# PSRAM_SPI.net
KiCad netlist of a schematic drawn in Altium Designer
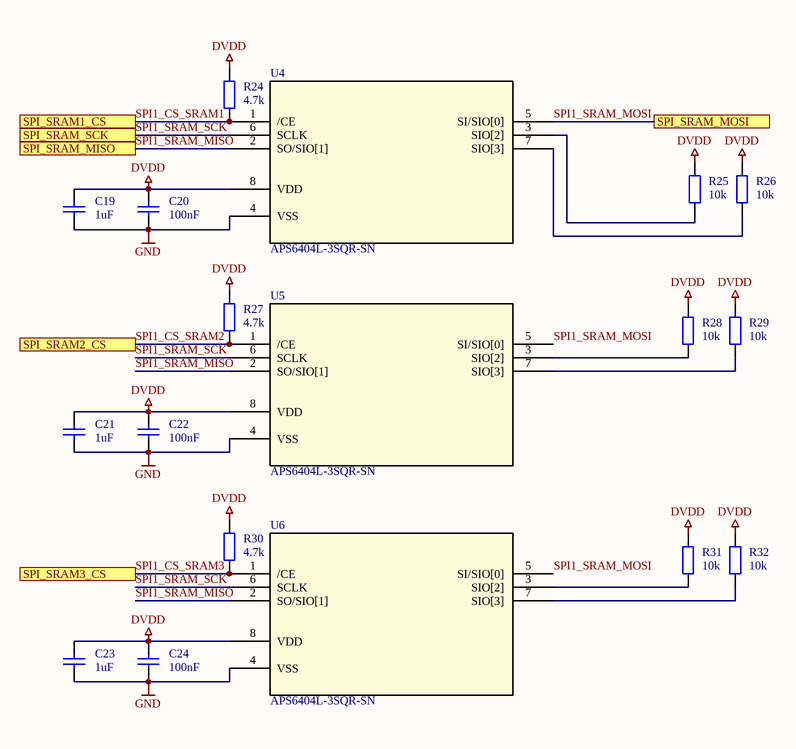
[diagram p0: PSRAM_SPI.SchDoc]

(export (version "E")
  (design (tool "Eeschema 10.0.6"))
  (components
    (comp (ref "C19")
      (value "1uF")
      (footprint "C1206-KUE")
      (description "Capacitor")
      (fields (field (name "MANUFACTURER") "Kemet") (field (name "PUBLISHER") "Altium Limited"))
      (libsource (lib "ExtrapartsKUE_V01") (part "Capacitor"))
    )
    (comp (ref "C20")
      (value "100nF")
      (footprint "C1206-KUE")
      (description "Capacitor")
      (fields (field (name "MANUFACTURER") "Kemet") (field (name "PUBLISHER") "Altium Limited"))
      (libsource (lib "ExtrapartsKUE_V01") (part "Capacitor"))
    )
    (comp (ref "C21")
      (value "1uF")
      (footprint "C1206-KUE")
      (description "Capacitor")
      (fields (field (name "MANUFACTURER") "Kemet") (field (name "PUBLISHER") "Altium Limited"))
      (libsource (lib "ExtrapartsKUE_V01") (part "Capacitor"))
    )
    (comp (ref "C22")
      (value "100nF")
      (footprint "C1206-KUE")
      (description "Capacitor")
      (fields (field (name "MANUFACTURER") "Kemet") (field (name "PUBLISHER") "Altium Limited"))
      (libsource (lib "ExtrapartsKUE_V01") (part "Capacitor"))
    )
    (comp (ref "C23")
      (value "1uF")
      (footprint "C1206-KUE")
      (description "Capacitor")
      (fields (field (name "MANUFACTURER") "Kemet") (field (name "PUBLISHER") "Altium Limited"))
      (libsource (lib "ExtrapartsKUE_V01") (part "Capacitor"))
    )
    (comp (ref "C24")
      (value "100nF")
      (footprint "C1206-KUE")
      (description "Capacitor")
      (fields (field (name "MANUFACTURER") "Kemet") (field (name "PUBLISHER") "Altium Limited"))
      (libsource (lib "ExtrapartsKUE_V01") (part "Capacitor"))
    )
    (comp (ref "R24")
      (value "4.7k")
      (footprint "C1206-KUE")
      (description "Resistor SMD")
      (fields (field (name "MANUFACTURER") "AVX") (field (name "PUBLISHER") "Altium Limited"))
      (libsource (lib "ExtrapartsKUE_V01") (part "ResistorSMD"))
    )
    (comp (ref "R25")
      (value "10k")
      (footprint "C1206-KUE")
      (description "Resistor SMD")
      (fields (field (name "MANUFACTURER") "AVX") (field (name "PUBLISHER") "Altium Limited"))
      (libsource (lib "ExtrapartsKUE_V01") (part "ResistorSMD"))
    )
    (comp (ref "R26")
      (value "10k")
      (footprint "C1206-KUE")
      (description "Resistor SMD")
      (fields (field (name "MANUFACTURER") "AVX") (field (name "PUBLISHER") "Altium Limited"))
      (libsource (lib "ExtrapartsKUE_V01") (part "ResistorSMD"))
    )
    (comp (ref "R27")
      (value "4.7k")
      (footprint "C1206-KUE")
      (description "Resistor SMD")
      (fields (field (name "MANUFACTURER") "AVX") (field (name "PUBLISHER") "Altium Limited"))
      (libsource (lib "ExtrapartsKUE_V01") (part "ResistorSMD"))
    )
    (comp (ref "R28")
      (value "10k")
      (footprint "C1206-KUE")
      (description "Resistor SMD")
      (fields (field (name "MANUFACTURER") "AVX") (field (name "PUBLISHER") "Altium Limited"))
      (libsource (lib "ExtrapartsKUE_V01") (part "ResistorSMD"))
    )
    (comp (ref "R29")
      (value "10k")
      (footprint "C1206-KUE")
      (description "Resistor SMD")
      (fields (field (name "MANUFACTURER") "AVX") (field (name "PUBLISHER") "Altium Limited"))
      (libsource (lib "ExtrapartsKUE_V01") (part "ResistorSMD"))
    )
    (comp (ref "R30")
      (value "4.7k")
      (footprint "C1206-KUE")
      (description "Resistor SMD")
      (fields (field (name "MANUFACTURER") "AVX") (field (name "PUBLISHER") "Altium Limited"))
      (libsource (lib "ExtrapartsKUE_V01") (part "ResistorSMD"))
    )
    (comp (ref "R31")
      (value "10k")
      (footprint "C1206-KUE")
      (description "Resistor SMD")
      (fields (field (name "MANUFACTURER") "AVX") (field (name "PUBLISHER") "Altium Limited"))
      (libsource (lib "ExtrapartsKUE_V01") (part "ResistorSMD"))
    )
    (comp (ref "R32")
      (value "10k")
      (footprint "C1206-KUE")
      (description "Resistor SMD")
      (fields (field (name "MANUFACTURER") "AVX") (field (name "PUBLISHER") "Altium Limited"))
      (libsource (lib "ExtrapartsKUE_V01") (part "ResistorSMD"))
    )
    (comp (ref "U4")
      (value "APS6404L-3SQR-SN")
      (footprint "APS6404L-3SQR-SN_APY")
      (description "Description")
      (fields (field (name "COPYRIGHT") "Copyright (C) 2025 Ultra Librarian. All rights reserved."))
      (libsource (lib "APS6404L-3SQR-SN") (part "APS6404L-3SQR-SN"))
    )
    (comp (ref "U5")
      (value "APS6404L-3SQR-SN")
      (footprint "APS6404L-3SQR-SN_APY")
      (description "Description")
      (fields (field (name "COPYRIGHT") "Copyright (C) 2025 Ultra Librarian. All rights reserved."))
      (libsource (lib "APS6404L-3SQR-SN") (part "APS6404L-3SQR-SN"))
    )
    (comp (ref "U6")
      (value "APS6404L-3SQR-SN")
      (footprint "APS6404L-3SQR-SN_APY")
      (description "Description")
      (fields (field (name "COPYRIGHT") "Copyright (C) 2025 Ultra Librarian. All rights reserved."))
      (libsource (lib "APS6404L-3SQR-SN") (part "APS6404L-3SQR-SN"))
    )
  )
  (nets
    (net (code "1") (name "/SPI1_CS_SRAM1") (class "Default")
      (node (ref "R24") (pin "2") (pinfunction "2_2") (pintype "passive"))
      (node (ref "U4") (pin "1") (pinfunction "/CE_1") (pintype "passive"))
    )
    (net (code "2") (name "/SPI1_CS_SRAM2") (class "Default")
      (node (ref "R27") (pin "2") (pinfunction "2_2") (pintype "passive"))
      (node (ref "U5") (pin "1") (pinfunction "/CE_1") (pintype "passive"))
    )
    (net (code "3") (name "/SPI1_CS_SRAM3") (class "Default")
      (node (ref "R30") (pin "2") (pinfunction "2_2") (pintype "passive"))
      (node (ref "U6") (pin "1") (pinfunction "/CE_1") (pintype "passive"))
    )
    (net (code "4") (name "/SPI1_SRAM_MISO") (class "Default")
      (node (ref "U4") (pin "2") (pinfunction "SO/SIO[1]_2") (pintype "passive"))
      (node (ref "U5") (pin "2") (pinfunction "SO/SIO[1]_2") (pintype "passive"))
      (node (ref "U6") (pin "2") (pinfunction "SO/SIO[1]_2") (pintype "passive"))
    )
    (net (code "5") (name "/SPI1_SRAM_MOSI") (class "Default")
      (node (ref "U4") (pin "5") (pinfunction "SI/SIO[0]_5") (pintype "passive"))
      (node (ref "U5") (pin "5") (pinfunction "SI/SIO[0]_5") (pintype "passive"))
      (node (ref "U6") (pin "5") (pinfunction "SI/SIO[0]_5") (pintype "passive"))
    )
    (net (code "6") (name "/SPI1_SRAM_SCK") (class "Default")
      (node (ref "U4") (pin "6") (pinfunction "SCLK_6") (pintype "passive"))
      (node (ref "U5") (pin "6") (pinfunction "SCLK_6") (pintype "passive"))
      (node (ref "U6") (pin "6") (pinfunction "SCLK_6") (pintype "passive"))
    )
    (net (code "7") (name "DVDD") (class "Default")
      (node (ref "C19") (pin "2") (pinfunction "2_2") (pintype "passive"))
      (node (ref "C20") (pin "2") (pinfunction "2_2") (pintype "passive"))
      (node (ref "C21") (pin "2") (pinfunction "2_2") (pintype "passive"))
      (node (ref "C22") (pin "2") (pinfunction "2_2") (pintype "passive"))
      (node (ref "C23") (pin "2") (pinfunction "2_2") (pintype "passive"))
      (node (ref "C24") (pin "2") (pinfunction "2_2") (pintype "passive"))
      (node (ref "R24") (pin "1") (pinfunction "1_1") (pintype "passive"))
      (node (ref "R25") (pin "1") (pinfunction "1_1") (pintype "passive"))
      (node (ref "R26") (pin "1") (pinfunction "1_1") (pintype "passive"))
      (node (ref "R27") (pin "1") (pinfunction "1_1") (pintype "passive"))
      (node (ref "R28") (pin "1") (pinfunction "1_1") (pintype "passive"))
      (node (ref "R29") (pin "1") (pinfunction "1_1") (pintype "passive"))
      (node (ref "R30") (pin "1") (pinfunction "1_1") (pintype "passive"))
      (node (ref "R31") (pin "1") (pinfunction "1_1") (pintype "passive"))
      (node (ref "R32") (pin "1") (pinfunction "1_1") (pintype "passive"))
      (node (ref "U4") (pin "8") (pinfunction "VDD_8") (pintype "passive"))
      (node (ref "U5") (pin "8") (pinfunction "VDD_8") (pintype "passive"))
      (node (ref "U6") (pin "8") (pinfunction "VDD_8") (pintype "passive"))
    )
    (net (code "8") (name "GND") (class "Default")
      (node (ref "C19") (pin "1") (pinfunction "1_1") (pintype "passive"))
      (node (ref "C20") (pin "1") (pinfunction "1_1") (pintype "passive"))
      (node (ref "C21") (pin "1") (pinfunction "1_1") (pintype "passive"))
      (node (ref "C22") (pin "1") (pinfunction "1_1") (pintype "passive"))
      (node (ref "C23") (pin "1") (pinfunction "1_1") (pintype "passive"))
      (node (ref "C24") (pin "1") (pinfunction "1_1") (pintype "passive"))
      (node (ref "U4") (pin "4") (pinfunction "VSS_4") (pintype "passive"))
      (node (ref "U5") (pin "4") (pinfunction "VSS_4") (pintype "passive"))
      (node (ref "U6") (pin "4") (pinfunction "VSS_4") (pintype "passive"))
    )
    (net (code "9") (name "Net-(U4-SIO[2])") (class "Default")
      (node (ref "R25") (pin "2") (pinfunction "2_2") (pintype "passive"))
      (node (ref "U4") (pin "3") (pinfunction "SIO[2]_3") (pintype "passive"))
    )
    (net (code "10") (name "Net-(U4-SIO[3])") (class "Default")
      (node (ref "R26") (pin "2") (pinfunction "2_2") (pintype "passive"))
      (node (ref "U4") (pin "7") (pinfunction "SIO[3]_7") (pintype "passive"))
    )
    (net (code "11") (name "Net-(U5-SIO[2])") (class "Default")
      (node (ref "R28") (pin "2") (pinfunction "2_2") (pintype "passive"))
      (node (ref "U5") (pin "3") (pinfunction "SIO[2]_3") (pintype "passive"))
    )
    (net (code "12") (name "Net-(U5-SIO[3])") (class "Default")
      (node (ref "R29") (pin "2") (pinfunction "2_2") (pintype "passive"))
      (node (ref "U5") (pin "7") (pinfunction "SIO[3]_7") (pintype "passive"))
    )
    (net (code "13") (name "Net-(U6-SIO[2])") (class "Default")
      (node (ref "R31") (pin "2") (pinfunction "2_2") (pintype "passive"))
      (node (ref "U6") (pin "3") (pinfunction "SIO[2]_3") (pintype "passive"))
    )
    (net (code "14") (name "Net-(U6-SIO[3])") (class "Default")
      (node (ref "R32") (pin "2") (pinfunction "2_2") (pintype "passive"))
      (node (ref "U6") (pin "7") (pinfunction "SIO[3]_7") (pintype "passive"))
    )
  )
)
